# multi-pcb-other.net
KiCad netlist of a schematic drawn in EAGLE
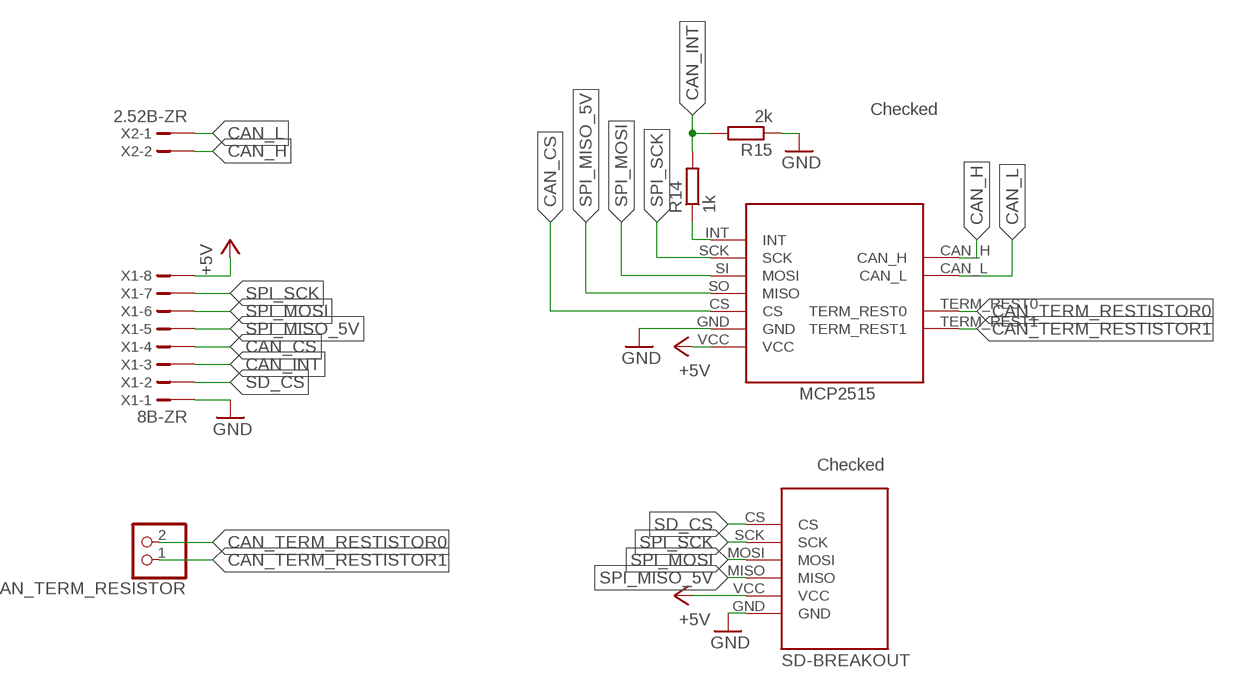
[diagram p0: schematic, sheet 1]

(export (version "E")
  (design (tool "Eeschema 10.0.6"))
  (components
    (comp (ref "CAN_TERM_RESISTOR")
      (value "PINHD-1X2")
      (footprint "eagle-import:1X02")
      (libsource (lib "eagle-import") (part "PINHD-1X2"))
    )
    (comp (ref "R14")
      (value "1k")
      (footprint "eagle-import:0207_10")
      (libsource (lib "eagle-import") (part "R-EU_0207/10"))
    )
    (comp (ref "R15")
      (value "2k")
      (footprint "eagle-import:0207_10")
      (libsource (lib "eagle-import") (part "R-EU_0207/10"))
    )
    (comp (ref "U$2")
      (value "MCP2515_DEVBOARDMCP2515_DEVBOARD_INVERTED_NODRILL")
      (footprint "eagle-import:MCP2515_DEVBOARD_INVERTED_NODRILL")
      (libsource (lib "eagle-import") (part "MCP2515_DEVBOARDMCP2515_DEVBOARD_INVERTED_NODRILL"))
    )
    (comp (ref "U$5")
      (value "HKD-MICRO-SD-BREAKOUT")
      (footprint "eagle-import:HKD-MICRO-SD-BREAKOUT_NODRILL")
      (libsource (lib "eagle-import") (part "HKD-MICRO-SD-BREAKOUT"))
    )
    (comp (ref "X1")
      (value "8B-ZR")
      (footprint "eagle-import:B8B-ZR2.5")
      (libsource (lib "eagle-import") (part "?8B-ZR"))
    )
    (comp (ref "X2")
      (value "2.52B-ZR")
      (footprint "eagle-import:B2B-ZR2.5")
      (libsource (lib "eagle-import") (part "?2B-ZR2.5"))
    )
  )
  (nets
    (net (code "1") (name "+5V") (class "Default")
      (node (ref "U$2") (pin "VCC") (pinfunction "VCC_VCC") (pintype "bidirectional"))
      (node (ref "U$5") (pin "VCC") (pinfunction "VCC_VCC") (pintype "bidirectional"))
      (node (ref "X1") (pin "8") (pinfunction "1_8") (pintype "passive"))
    )
    (net (code "2") (name "CAN_CS") (class "Default")
      (node (ref "U$2") (pin "CS") (pinfunction "CS_CS") (pintype "input"))
      (node (ref "X1") (pin "4") (pinfunction "1_4") (pintype "passive"))
    )
    (net (code "3") (name "CAN_H") (class "Default")
      (node (ref "U$2") (pin "CAN_H") (pinfunction "CAN_H_CAN_H") (pintype "bidirectional"))
      (node (ref "X2") (pin "2") (pinfunction "1_2") (pintype "passive"))
    )
    (net (code "4") (name "CAN_INT") (class "Default")
      (node (ref "R14") (pin "2") (pinfunction "2_2") (pintype "passive"))
      (node (ref "R15") (pin "2") (pinfunction "2_2") (pintype "passive"))
      (node (ref "X1") (pin "3") (pinfunction "1_3") (pintype "passive"))
    )
    (net (code "5") (name "CAN_L") (class "Default")
      (node (ref "U$2") (pin "CAN_L") (pinfunction "CAN_L_CAN_L") (pintype "bidirectional"))
      (node (ref "X2") (pin "1") (pinfunction "1_1") (pintype "passive"))
    )
    (net (code "6") (name "CAN_TERM_RESTISTOR0") (class "Default")
      (node (ref "CAN_TERM_RESISTOR") (pin "2") (pinfunction "2_2") (pintype "passive"))
      (node (ref "U$2") (pin "TERM_REST0") (pinfunction "TERM_REST0_TERM_REST0") (pintype "bidirectional"))
    )
    (net (code "7") (name "CAN_TERM_RESTISTOR1") (class "Default")
      (node (ref "CAN_TERM_RESISTOR") (pin "1") (pinfunction "1_1") (pintype "passive"))
      (node (ref "U$2") (pin "TERM_REST1") (pinfunction "TERM_REST1_TERM_REST1") (pintype "bidirectional"))
    )
    (net (code "8") (name "GND") (class "Default")
      (node (ref "R15") (pin "1") (pinfunction "1_1") (pintype "passive"))
      (node (ref "U$2") (pin "GND") (pinfunction "GND_GND") (pintype "bidirectional"))
      (node (ref "U$5") (pin "GND") (pinfunction "GND_GND") (pintype "bidirectional"))
      (node (ref "X1") (pin "1") (pinfunction "1_1") (pintype "passive"))
    )
    (net (code "9") (name "Net-(R14-Pad1)") (class "Default")
      (node (ref "R14") (pin "1") (pinfunction "1_1") (pintype "passive"))
      (node (ref "U$2") (pin "INT") (pinfunction "INT_INT") (pintype "output"))
    )
    (net (code "10") (name "SD_CS") (class "Default")
      (node (ref "U$5") (pin "CS") (pinfunction "CS_CS") (pintype "bidirectional"))
      (node (ref "X1") (pin "2") (pinfunction "1_2") (pintype "passive"))
    )
    (net (code "11") (name "SPI_MISO_5V") (class "Default")
      (node (ref "U$2") (pin "SO") (pinfunction "MISO_SO") (pintype "output"))
      (node (ref "U$5") (pin "MISO") (pinfunction "MISO_MISO") (pintype "bidirectional"))
      (node (ref "X1") (pin "5") (pinfunction "1_5") (pintype "passive"))
    )
    (net (code "12") (name "SPI_MOSI") (class "Default")
      (node (ref "U$2") (pin "SI") (pinfunction "MOSI_SI") (pintype "input"))
      (node (ref "U$5") (pin "MOSI") (pinfunction "MOSI_MOSI") (pintype "bidirectional"))
      (node (ref "X1") (pin "6") (pinfunction "1_6") (pintype "passive"))
    )
    (net (code "13") (name "SPI_SCK") (class "Default")
      (node (ref "U$2") (pin "SCK") (pinfunction "SCK_SCK") (pintype "input"))
      (node (ref "U$5") (pin "SCK") (pinfunction "SCK_SCK") (pintype "bidirectional"))
      (node (ref "X1") (pin "7") (pinfunction "1_7") (pintype "passive"))
    )
  )
)
